# schematic.net
KiCad netlist of a schematic drawn in EasyEDA
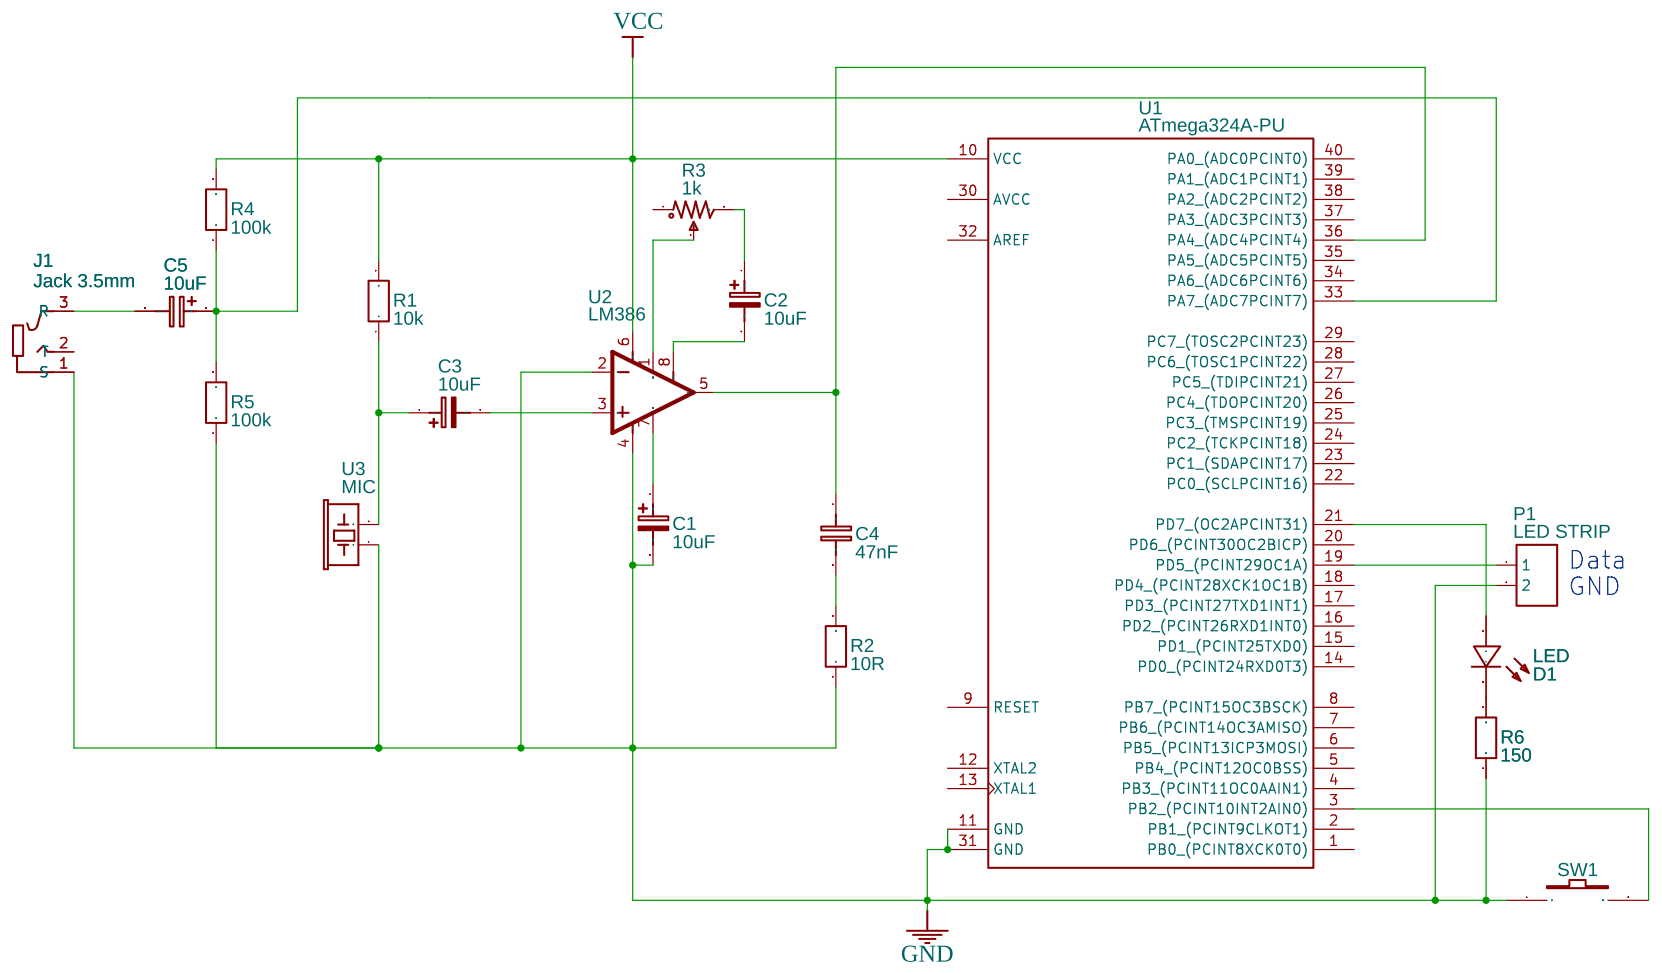
[diagram p0: schematic sheet]

(export (version "E")
  (design (tool "Eeschema 10.0.6"))
  (components
    (comp (ref "C1")
      (value "10uF")
      (fields (field (name "BOM_Manufacturer Part") "?"))
      (libsource (lib "") (part "Cap_Electrolytic(TH)_D3.0XF1.5_EU"))
    )
    (comp (ref "C2")
      (value "10uF")
      (fields (field (name "BOM_Manufacturer Part") "?"))
      (libsource (lib "") (part "Cap_Electrolytic(TH)_D3.0XF1.5_EU_3"))
    )
    (comp (ref "C3")
      (value "10uF")
      (fields (field (name "BOM_Manufacturer Part") "?"))
      (libsource (lib "") (part "Cap_Electrolytic(TH)_D3.0XF1.5_EU_2"))
    )
    (comp (ref "C4")
      (value "47nF")
      (fields (field (name "BOM_Manufacturer Part") "?"))
      (libsource (lib "") (part "Cap_RAD-0.1_EU"))
    )
    (comp (ref "C5")
      (value "10uF")
      (fields (field (name "BOM_Manufacturer Part") "?"))
      (libsource (lib "") (part "Cap_Electrolytic(TH)_D3.0XF1.5_EU_1"))
    )
    (comp (ref "J1")
      (value "Jack 3.5mm")
      (fields (field (name "BOM_Manufacturer Part") "?"))
      (libsource (lib "") (part "Unknown_160_265"))
    )
    (comp (ref "LED")
      (value "D1")
      (fields
        (field (name "BOM_Manufacturer Part") "204-10SURD/S530-A3")
        (field (name "BOM_Supplier Part") "C99772")
      )
      (libsource (lib "") (part "Unknown_875_420"))
    )
    (comp (ref "P1")
      (value "LED STRIP")
      (fields
        (field (name "BOM_Manufacturer Part") "2.54-1*2PFemale")
        (field (name "BOM_Supplier Part") "C49661")
      )
      (libsource (lib "") (part "Unknown_890_380"))
    )
    (comp (ref "R1")
      (value "10k")
      (fields (field (name "BOM_Manufacturer Part") "?"))
      (libsource (lib "") (part "Res_AXIAL-0.3(1/8W)_EU"))
    )
    (comp (ref "R2")
      (value "10R")
      (fields (field (name "BOM_Manufacturer Part") "?"))
      (libsource (lib "") (part "Res_AXIAL-0.3(1/8W)_EU"))
    )
    (comp (ref "R3")
      (value "1k")
      (fields
        (field (name "BOM_Manufacturer Part") "3386P-1-101LF")
        (field (name "BOM_Supplier Part") "C125022")
      )
      (libsource (lib "") (part "3386P-1-101LF_US"))
    )
    (comp (ref "R4")
      (value "100k")
      (fields (field (name "BOM_Manufacturer Part") "?"))
      (libsource (lib "") (part "Res_AXIAL-0.3(1/8W)_EU"))
    )
    (comp (ref "R5")
      (value "100k")
      (fields (field (name "BOM_Manufacturer Part") "?"))
      (libsource (lib "") (part "Res_AXIAL-0.3(1/8W)_EU"))
    )
    (comp (ref "R6")
      (value "150")
      (fields (field (name "BOM_Manufacturer Part") "?"))
      (libsource (lib "") (part "Res_AXIAL-0.3(1/8W)_EU"))
    )
    (comp (ref "SW1")
      (value "EVQ22705R")
      (fields (field (name "BOM_Supplier Part") "C79156"))
      (libsource (lib "") (part "Unknown_915_540"))
    )
    (comp (ref "U1")
      (value "ATmega324A-PU")
      (fields (field (name "BOM_Manufacturer Part") "?"))
      (libsource (lib "") (part "Unknown_705_345"))
    )
    (comp (ref "U2")
      (value "LM386")
      (fields (field (name "BOM_Manufacturer Part") "?"))
      (libsource (lib "") (part "Unknown_460_290"))
    )
    (comp (ref "U3")
      (value "MIC")
      (fields (field (name "BOM_Manufacturer Part") "?"))
      (libsource (lib "") (part "Unknown_315_360"))
    )
  )
  (nets
    (net (code "1") (name "GND") (class "Default")
      (node (ref "C1") (pin "2") (pinfunction "2_2") (pintype "unspecified"))
      (node (ref "J1") (pin "1") (pinfunction "S_1") (pintype "unspecified"))
      (node (ref "P1") (pin "2") (pinfunction "2_2") (pintype "input"))
      (node (ref "R2") (pin "1") (pinfunction "1_1") (pintype "unspecified"))
      (node (ref "R5") (pin "1") (pinfunction "1_1") (pintype "unspecified"))
      (node (ref "R6") (pin "1") (pinfunction "1_1") (pintype "unspecified"))
      (node (ref "SW1") (pin "1") (pinfunction "1_1") (pintype "input"))
      (node (ref "U1") (pin "11") (pinfunction "GND_11") (pintype "passive"))
      (node (ref "U1") (pin "31") (pinfunction "GND_31") (pintype "passive"))
      (node (ref "U2") (pin "2") (pinfunction "-IN_2") (pintype "input"))
      (node (ref "U2") (pin "4") (pinfunction "V-_4") (pintype "passive"))
      (node (ref "U3") (pin "1") (pinfunction "1_1") (pintype "unspecified"))
    )
    (net (code "2") (name "Net-(C2-Pad1)") (class "Default")
      (node (ref "C2") (pin "1") (pinfunction "1_1") (pintype "unspecified"))
      (node (ref "R3") (pin "3") (pinfunction "3_3") (pintype "unspecified"))
    )
    (net (code "3") (name "Net-(C2-Pad2)") (class "Default")
      (node (ref "C2") (pin "2") (pinfunction "2_2") (pintype "unspecified"))
      (node (ref "U2") (pin "8") (pinfunction "GAIN_8") (pintype "unspecified"))
    )
    (net (code "4") (name "Net-(C3-Pad1)") (class "Default")
      (node (ref "C3") (pin "1") (pinfunction "1_1") (pintype "unspecified"))
      (node (ref "R1") (pin "1") (pinfunction "1_1") (pintype "unspecified"))
      (node (ref "U3") (pin "2") (pinfunction "2_2") (pintype "unspecified"))
    )
    (net (code "5") (name "Net-(C4-Pad2)") (class "Default")
      (node (ref "C4") (pin "2") (pinfunction "2_2") (pintype "unspecified"))
      (node (ref "R2") (pin "2") (pinfunction "2_2") (pintype "unspecified"))
    )
    (net (code "6") (name "Net-(J1-R)") (class "Default")
      (node (ref "C5") (pin "2") (pinfunction "2_2") (pintype "unspecified"))
      (node (ref "J1") (pin "3") (pinfunction "R_3") (pintype "unspecified"))
    )
    (net (code "7") (name "Net-(LED-+)") (class "Default")
      (node (ref "LED") (pin "1") (pinfunction "+_1") (pintype "unspecified"))
      (node (ref "U1") (pin "21") (pinfunction "PD7_(OC2APCINT31)_21") (pintype "bidirectional"))
    )
    (net (code "8") (name "Net-(LED--)") (class "Default")
      (node (ref "LED") (pin "2") (pinfunction "-_2") (pintype "unspecified"))
      (node (ref "R6") (pin "2") (pinfunction "2_2") (pintype "unspecified"))
    )
    (net (code "9") (name "Net-(R3-Pad2)") (class "Default")
      (node (ref "R3") (pin "2") (pinfunction "2_2") (pintype "unspecified"))
      (node (ref "U2") (pin "1") (pinfunction "GAIN_1") (pintype "unspecified"))
    )
    (net (code "10") (name "Net-(U1-PA4_(ADC4PCINT4))") (class "Default")
      (node (ref "C4") (pin "1") (pinfunction "1_1") (pintype "unspecified"))
      (node (ref "U1") (pin "36") (pinfunction "PA4_(ADC4PCINT4)_36") (pintype "bidirectional"))
      (node (ref "U2") (pin "5") (pinfunction "OUT_5") (pintype "output"))
    )
    (net (code "11") (name "Net-(U1-PA7_(ADC7PCINT7))") (class "Default")
      (node (ref "C5") (pin "1") (pinfunction "1_1") (pintype "unspecified"))
      (node (ref "R4") (pin "1") (pinfunction "1_1") (pintype "unspecified"))
      (node (ref "R5") (pin "2") (pinfunction "2_2") (pintype "unspecified"))
      (node (ref "U1") (pin "33") (pinfunction "PA7_(ADC7PCINT7)_33") (pintype "bidirectional"))
    )
    (net (code "12") (name "Net-(U1-PB2_(PCINT10INT2AIN0))") (class "Default")
      (node (ref "SW1") (pin "2") (pinfunction "2_2") (pintype "input"))
      (node (ref "U1") (pin "3") (pinfunction "PB2_(PCINT10INT2AIN0)_3") (pintype "bidirectional"))
    )
    (net (code "13") (name "Net-(U1-PD5_(PCINT29OC1A))") (class "Default")
      (node (ref "P1") (pin "1") (pinfunction "1_1") (pintype "input"))
      (node (ref "U1") (pin "19") (pinfunction "PD5_(PCINT29OC1A)_19") (pintype "bidirectional"))
    )
    (net (code "14") (name "Net-(U2-+IN)") (class "Default")
      (node (ref "C3") (pin "2") (pinfunction "2_2") (pintype "unspecified"))
      (node (ref "U2") (pin "3") (pinfunction "+IN_3") (pintype "input"))
    )
    (net (code "15") (name "Net-(U2-BP)") (class "Default")
      (node (ref "C1") (pin "1") (pinfunction "1_1") (pintype "unspecified"))
      (node (ref "U2") (pin "7") (pinfunction "BP_7") (pintype "unspecified"))
    )
    (net (code "16") (name "VCC") (class "Default")
      (node (ref "R1") (pin "2") (pinfunction "2_2") (pintype "unspecified"))
      (node (ref "R4") (pin "2") (pinfunction "2_2") (pintype "unspecified"))
      (node (ref "U1") (pin "10") (pinfunction "VCC_10") (pintype "passive"))
      (node (ref "U2") (pin "6") (pinfunction "V+_6") (pintype "passive"))
    )
    (net (code "17") (name "unconnected-(J1-T-Pad2)") (class "Default")
      (node (ref "J1") (pin "2") (pinfunction "T_2") (pintype "unspecified"))
    )
    (net (code "18") (name "unconnected-(R3-Pad1)") (class "Default")
      (node (ref "R3") (pin "1") (pinfunction "1_1") (pintype "unspecified"))
    )
    (net (code "19") (name "unconnected-(U1-AREF-Pad32)") (class "Default")
      (node (ref "U1") (pin "32") (pinfunction "AREF_32") (pintype "passive"))
    )
    (net (code "20") (name "unconnected-(U1-AVCC-Pad30)") (class "Default")
      (node (ref "U1") (pin "30") (pinfunction "AVCC_30") (pintype "passive"))
    )
    (net (code "21") (name "unconnected-(U1-PA0_(ADC0PCINT0)-Pad40)") (class "Default")
      (node (ref "U1") (pin "40") (pinfunction "PA0_(ADC0PCINT0)_40") (pintype "bidirectional"))
    )
    (net (code "22") (name "unconnected-(U1-PA1_(ADC1PCINT1)-Pad39)") (class "Default")
      (node (ref "U1") (pin "39") (pinfunction "PA1_(ADC1PCINT1)_39") (pintype "bidirectional"))
    )
    (net (code "23") (name "unconnected-(U1-PA2_(ADC2PCINT2)-Pad38)") (class "Default")
      (node (ref "U1") (pin "38") (pinfunction "PA2_(ADC2PCINT2)_38") (pintype "bidirectional"))
    )
    (net (code "24") (name "unconnected-(U1-PA3_(ADC3PCINT3)-Pad37)") (class "Default")
      (node (ref "U1") (pin "37") (pinfunction "PA3_(ADC3PCINT3)_37") (pintype "bidirectional"))
    )
    (net (code "25") (name "unconnected-(U1-PA5_(ADC5PCINT5)-Pad35)") (class "Default")
      (node (ref "U1") (pin "35") (pinfunction "PA5_(ADC5PCINT5)_35") (pintype "bidirectional"))
    )
    (net (code "26") (name "unconnected-(U1-PA6_(ADC6PCINT6)-Pad34)") (class "Default")
      (node (ref "U1") (pin "34") (pinfunction "PA6_(ADC6PCINT6)_34") (pintype "bidirectional"))
    )
    (net (code "27") (name "unconnected-(U1-PB0_(PCINT8XCK0T0)-Pad1)") (class "Default")
      (node (ref "U1") (pin "1") (pinfunction "PB0_(PCINT8XCK0T0)_1") (pintype "bidirectional"))
    )
    (net (code "28") (name "unconnected-(U1-PB1_(PCINT9CLKOT1)-Pad2)") (class "Default")
      (node (ref "U1") (pin "2") (pinfunction "PB1_(PCINT9CLKOT1)_2") (pintype "bidirectional"))
    )
    (net (code "29") (name "unconnected-(U1-PB3_(PCINT11OC0AAIN1)-Pad4)") (class "Default")
      (node (ref "U1") (pin "4") (pinfunction "PB3_(PCINT11OC0AAIN1)_4") (pintype "bidirectional"))
    )
    (net (code "30") (name "unconnected-(U1-PB4_(PCINT12OC0BSS)-Pad5)") (class "Default")
      (node (ref "U1") (pin "5") (pinfunction "PB4_(PCINT12OC0BSS)_5") (pintype "bidirectional"))
    )
    (net (code "31") (name "unconnected-(U1-PB5_(PCINT13ICP3MOSI)-Pad6)") (class "Default")
      (node (ref "U1") (pin "6") (pinfunction "PB5_(PCINT13ICP3MOSI)_6") (pintype "bidirectional"))
    )
    (net (code "32") (name "unconnected-(U1-PB6_(PCINT14OC3AMISO)-Pad7)") (class "Default")
      (node (ref "U1") (pin "7") (pinfunction "PB6_(PCINT14OC3AMISO)_7") (pintype "bidirectional"))
    )
    (net (code "33") (name "unconnected-(U1-PB7_(PCINT15OC3BSCK)-Pad8)") (class "Default")
      (node (ref "U1") (pin "8") (pinfunction "PB7_(PCINT15OC3BSCK)_8") (pintype "bidirectional"))
    )
    (net (code "34") (name "unconnected-(U1-PC0_(SCLPCINT16)-Pad22)") (class "Default")
      (node (ref "U1") (pin "22") (pinfunction "PC0_(SCLPCINT16)_22") (pintype "bidirectional"))
    )
    (net (code "35") (name "unconnected-(U1-PC1_(SDAPCINT17)-Pad23)") (class "Default")
      (node (ref "U1") (pin "23") (pinfunction "PC1_(SDAPCINT17)_23") (pintype "bidirectional"))
    )
    (net (code "36") (name "unconnected-(U1-PC2_(TCKPCINT18)-Pad24)") (class "Default")
      (node (ref "U1") (pin "24") (pinfunction "PC2_(TCKPCINT18)_24") (pintype "bidirectional"))
    )
    (net (code "37") (name "unconnected-(U1-PC3_(TMSPCINT19)-Pad25)") (class "Default")
      (node (ref "U1") (pin "25") (pinfunction "PC3_(TMSPCINT19)_25") (pintype "bidirectional"))
    )
    (net (code "38") (name "unconnected-(U1-PC4_(TDOPCINT20)-Pad26)") (class "Default")
      (node (ref "U1") (pin "26") (pinfunction "PC4_(TDOPCINT20)_26") (pintype "bidirectional"))
    )
    (net (code "39") (name "unconnected-(U1-PC5_(TDIPCINT21)-Pad27)") (class "Default")
      (node (ref "U1") (pin "27") (pinfunction "PC5_(TDIPCINT21)_27") (pintype "bidirectional"))
    )
    (net (code "40") (name "unconnected-(U1-PC6_(TOSC1PCINT22)-Pad28)") (class "Default")
      (node (ref "U1") (pin "28") (pinfunction "PC6_(TOSC1PCINT22)_28") (pintype "bidirectional"))
    )
    (net (code "41") (name "unconnected-(U1-PC7_(TOSC2PCINT23)-Pad29)") (class "Default")
      (node (ref "U1") (pin "29") (pinfunction "PC7_(TOSC2PCINT23)_29") (pintype "bidirectional"))
    )
    (net (code "42") (name "unconnected-(U1-PD0_(PCINT24RXD0T3)-Pad14)") (class "Default")
      (node (ref "U1") (pin "14") (pinfunction "PD0_(PCINT24RXD0T3)_14") (pintype "bidirectional"))
    )
    (net (code "43") (name "unconnected-(U1-PD1_(PCINT25TXD0)-Pad15)") (class "Default")
      (node (ref "U1") (pin "15") (pinfunction "PD1_(PCINT25TXD0)_15") (pintype "bidirectional"))
    )
    (net (code "44") (name "unconnected-(U1-PD2_(PCINT26RXD1INT0)-Pad16)") (class "Default")
      (node (ref "U1") (pin "16") (pinfunction "PD2_(PCINT26RXD1INT0)_16") (pintype "bidirectional"))
    )
    (net (code "45") (name "unconnected-(U1-PD3_(PCINT27TXD1INT1)-Pad17)") (class "Default")
      (node (ref "U1") (pin "17") (pinfunction "PD3_(PCINT27TXD1INT1)_17") (pintype "bidirectional"))
    )
    (net (code "46") (name "unconnected-(U1-PD4_(PCINT28XCK1OC1B)-Pad18)") (class "Default")
      (node (ref "U1") (pin "18") (pinfunction "PD4_(PCINT28XCK1OC1B)_18") (pintype "bidirectional"))
    )
    (net (code "47") (name "unconnected-(U1-PD6_(PCINT30OC2BICP)-Pad20)") (class "Default")
      (node (ref "U1") (pin "20") (pinfunction "PD6_(PCINT30OC2BICP)_20") (pintype "bidirectional"))
    )
    (net (code "48") (name "unconnected-(U1-RESET-Pad9)") (class "Default")
      (node (ref "U1") (pin "9") (pinfunction "RESET_9") (pintype "unspecified"))
    )
    (net (code "49") (name "unconnected-(U1-XTAL1-Pad13)") (class "Default")
      (node (ref "U1") (pin "13") (pinfunction "XTAL1_13") (pintype "unspecified"))
    )
    (net (code "50") (name "unconnected-(U1-XTAL2-Pad12)") (class "Default")
      (node (ref "U1") (pin "12") (pinfunction "XTAL2_12") (pintype "output"))
    )
  )
)
